# AltiumSTM32_Barunastra.net
KiCad netlist of a schematic drawn in Altium Designer
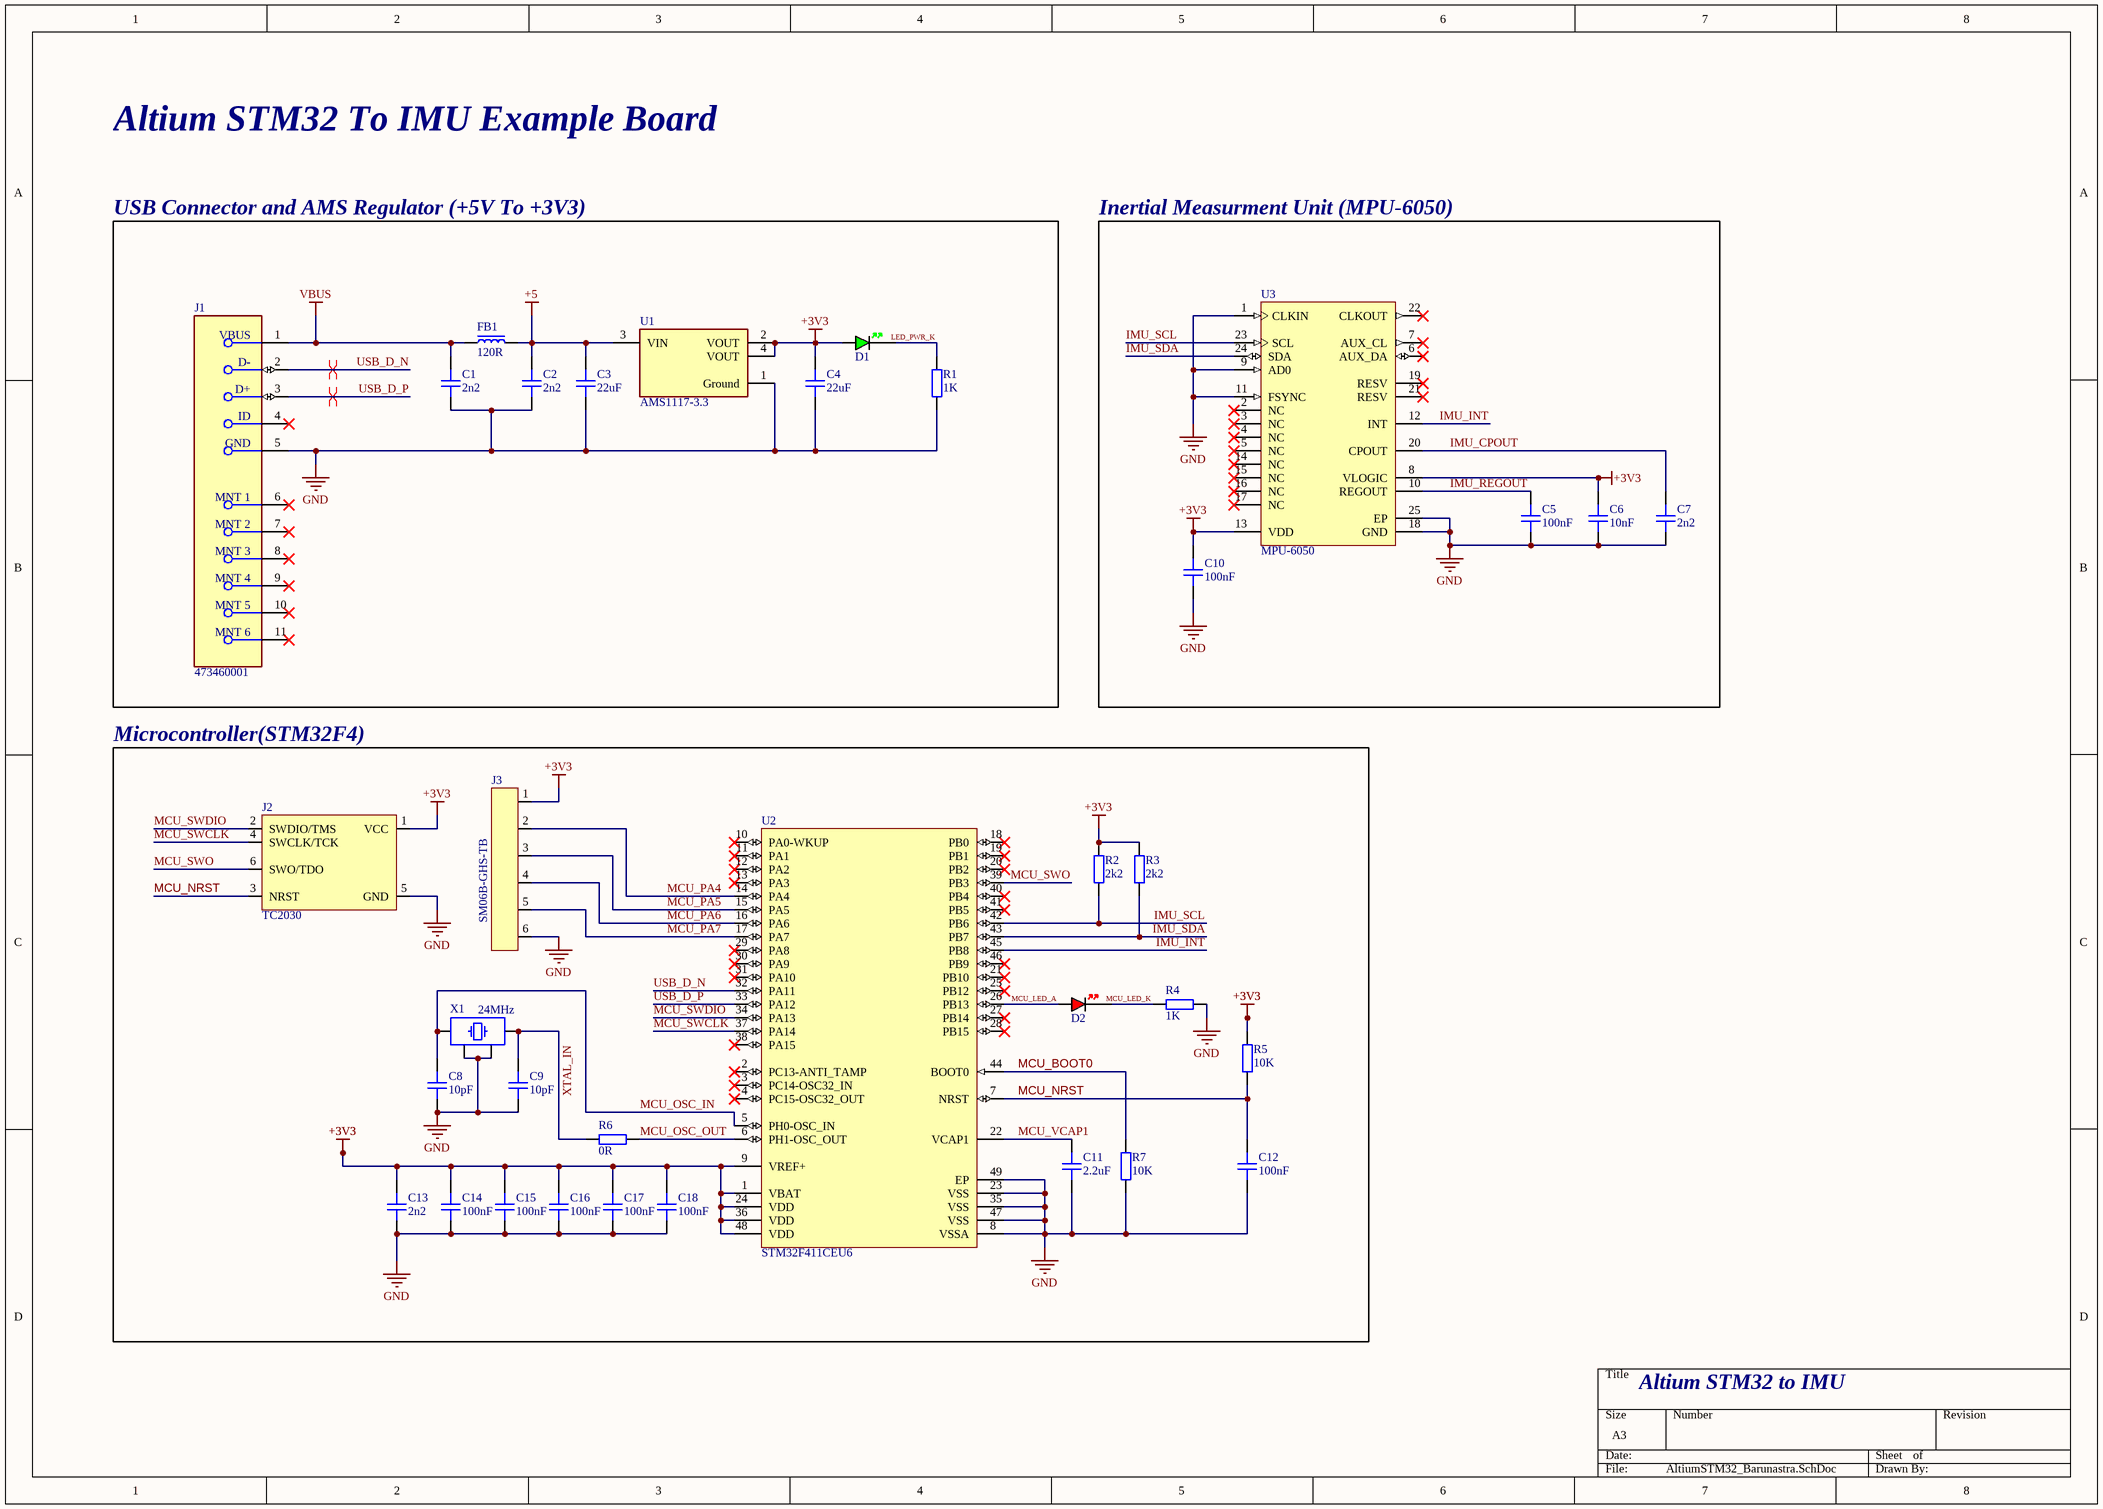
[diagram p0: AltiumSTM32_Barunastra.SchDoc]

(export (version "E")
  (design (tool "Eeschema 10.0.6"))
  (components
    (comp (ref "C1")
      (value "2n2")
      (footprint "CAP_0603")
      (description "Capacitor SMD 0603")
      (libsource (lib "Schematic-Lib-PhilsLab") (part "CAP_0603"))
    )
    (comp (ref "C2")
      (value "2n2")
      (footprint "CAP_0603")
      (description "Capacitor SMD 0603")
      (libsource (lib "Schematic-Lib-PhilsLab") (part "CAP_0603"))
    )
    (comp (ref "C3")
      (value "22uF")
      (footprint "CAP_0805")
      (description "Capacitor SMD 0805")
      (libsource (lib "Schematic-Lib-PhilsLab") (part "CAP_0805"))
    )
    (comp (ref "C4")
      (value "22uF")
      (footprint "CAP_0805")
      (description "Capacitor SMD 0805")
      (libsource (lib "Schematic-Lib-PhilsLab") (part "CAP_0805"))
    )
    (comp (ref "C5")
      (value "100nF")
      (footprint "CAP_0402")
      (description "Capacitor SMD 0402")
      (libsource (lib "Schematic-Lib-PhilsLab") (part "CAP_0402"))
    )
    (comp (ref "C6")
      (value "10nF")
      (footprint "CAP_0402")
      (description "Capacitor SMD 0402")
      (libsource (lib "Schematic-Lib-PhilsLab") (part "CAP_0402"))
    )
    (comp (ref "C7")
      (value "2n2")
      (footprint "CAP_0402")
      (description "Capacitor SMD 0402")
      (libsource (lib "Schematic-Lib-PhilsLab") (part "CAP_0402"))
    )
    (comp (ref "C8")
      (value "10pF")
      (footprint "CAP_0402")
      (description "Capacitor SMD 0402")
      (libsource (lib "Schematic-Lib-PhilsLab") (part "CAP_0402"))
    )
    (comp (ref "C9")
      (value "10pF")
      (footprint "CAP_0402")
      (description "Capacitor SMD 0402")
      (libsource (lib "Schematic-Lib-PhilsLab") (part "CAP_0402"))
    )
    (comp (ref "C10")
      (value "100nF")
      (footprint "CAP_0402")
      (description "Capacitor SMD 0402")
      (libsource (lib "Schematic-Lib-PhilsLab") (part "CAP_0402"))
    )
    (comp (ref "C11")
      (value "2.2uF")
      (footprint "CAP_0603")
      (description "Capacitor SMD 0603")
      (libsource (lib "Schematic-Lib-PhilsLab") (part "CAP_0603"))
    )
    (comp (ref "C12")
      (value "100nF")
      (footprint "CAP_0402")
      (description "Capacitor SMD 0402")
      (libsource (lib "Schematic-Lib-PhilsLab") (part "CAP_0402"))
    )
    (comp (ref "C13")
      (value "2n2")
      (footprint "CAP_0603")
      (description "Capacitor SMD 0603")
      (libsource (lib "Schematic-Lib-PhilsLab") (part "CAP_0603"))
    )
    (comp (ref "C14")
      (value "100nF")
      (footprint "CAP_0402")
      (description "Capacitor SMD 0402")
      (libsource (lib "Schematic-Lib-PhilsLab") (part "CAP_0402"))
    )
    (comp (ref "C15")
      (value "100nF")
      (footprint "CAP_0402")
      (description "Capacitor SMD 0402")
      (libsource (lib "Schematic-Lib-PhilsLab") (part "CAP_0402"))
    )
    (comp (ref "C16")
      (value "100nF")
      (footprint "CAP_0402")
      (description "Capacitor SMD 0402")
      (libsource (lib "Schematic-Lib-PhilsLab") (part "CAP_0402"))
    )
    (comp (ref "C17")
      (value "100nF")
      (footprint "CAP_0402")
      (description "Capacitor SMD 0402")
      (libsource (lib "Schematic-Lib-PhilsLab") (part "CAP_0402"))
    )
    (comp (ref "C18")
      (value "100nF")
      (footprint "CAP_0402")
      (description "Capacitor SMD 0402")
      (libsource (lib "Schematic-Lib-PhilsLab") (part "CAP_0402"))
    )
    (comp (ref "D1")
      (value "GREEN")
      (footprint "LED_0402_GREEN")
      (description "LED 0402 GREEN SMD")
      (libsource (lib "Schematic-Lib-PhilsLab") (part "LED_0402_GREEN"))
    )
    (comp (ref "D2")
      (value "RED")
      (footprint "LED_0402_RED")
      (description "LED 0402 RED SMD")
      (libsource (lib "Schematic-Lib-PhilsLab") (part "LED_0402_RED"))
    )
    (comp (ref "FB1")
      (value "120R")
      (footprint "FB_0603")
      (description "Ferrite Bead SMD 0603")
      (libsource (lib "Schematic-Lib-PhilsLab") (part "FB_0603"))
    )
    (comp (ref "J1")
      (value "473460001")
      (footprint "FP-473460001-MFG")
      (description "CONN RCPT USB2.0 MICRO B SMD R/A")
      (fields
        (field (name "OCTOPART") "https://octopart.com/47346-0001-molex-7164928")
        (field (name "MANUFACTURER") "Molex")
      )
      (libsource (lib "Altium Content Vault") (part "53ae1f1d9b557310b43ca686e5bb76a"))
    )
    (comp (ref "J2")
      (value "TC2030")
      (footprint "TC2030-FP")
      (description "Tag-Connect No-Solder SWD Debug Connector DO NOT PLACE")
      (fields (field (name "MANUFACTURER") "Tag-Connect"))
      (libsource (lib "Schematic-Lib-PhilsLab") (part "TC2030"))
    )
    (comp (ref "J3")
      (value "SM06B-GHS-TB")
      (footprint "SM06B-GHS-TB")
      (description "Header Connector 6 Position 1.25MM Pitch SMD Horizontal JST GH")
      (fields (field (name "MANUFACTURER") "JST"))
      (libsource (lib "Schematic-Lib-PhilsLab") (part "SM06B-GHS-TB"))
    )
    (comp (ref "R1")
      (value "1K")
      (footprint "RES_0402")
      (description "Resistor SMD 0402")
      (libsource (lib "Schematic-Lib-PhilsLab") (part "RES_0402"))
    )
    (comp (ref "R2")
      (value "2k2")
      (footprint "RES_0402")
      (description "Resistor SMD 0402")
      (libsource (lib "Schematic-Lib-PhilsLab") (part "RES_0402"))
    )
    (comp (ref "R3")
      (value "2k2")
      (footprint "RES_0402")
      (description "Resistor SMD 0402")
      (libsource (lib "Schematic-Lib-PhilsLab") (part "RES_0402"))
    )
    (comp (ref "R4")
      (value "1K")
      (footprint "RES_0402")
      (description "Resistor SMD 0402")
      (libsource (lib "Schematic-Lib-PhilsLab") (part "RES_0402"))
    )
    (comp (ref "R5")
      (value "10K")
      (footprint "RES_0402")
      (description "Resistor SMD 0402")
      (libsource (lib "Schematic-Lib-PhilsLab") (part "RES_0402"))
    )
    (comp (ref "R6")
      (value "0R")
      (footprint "RES_0402")
      (description "Resistor SMD 0402")
      (libsource (lib "Schematic-Lib-PhilsLab") (part "RES_0402"))
    )
    (comp (ref "R7")
      (value "10K")
      (footprint "RES_0402")
      (description "Resistor SMD 0402")
      (libsource (lib "Schematic-Lib-PhilsLab") (part "RES_0402"))
    )
    (comp (ref "U1")
      (value "AMS1117-3.3")
      (footprint "FP-AMS1117-IPC_C")
      (description "LDO Voltage Regulators 1A, 3.3V")
      (fields
        (field (name "OCTOPART") "https://octopart.com/ams1117-3.3-advanced+monolithic+systems-25899300")
        (field (name "MANUFACTURER") "Advanced Monolithic Systems")
      )
      (libsource (lib "Altium Content Vault") (part "8bdbb5f8e77002000e30dd2845d0354"))
    )
    (comp (ref "U2")
      (value "STM32F411CEU6")
      (footprint "STM-UFQFPN48_L")
      (libsource (lib "Altium Content Vault") (part "MC-ARM-STM32F411-UFQFPN48"))
    )
    (comp (ref "U3")
      (value "MPU-6050")
      (footprint "IS-QFN-24_V")
      (fields (field (name "MANUFACTURER") "InvenSense"))
      (libsource (lib "Altium Content Vault") (part "IS-MPU-6050-QFN-24"))
    )
    (comp (ref "X1")
      (value "24MHz")
      (footprint "XTAL_3225")
      (description "Crystal SMD 24MHz 10PPM 7pF 3225")
      (fields
        (field (name "MANUFACTURER") "Epson")
        (field (name "MANUFACTURER PART NUMBER") "TSX-3225 24.0000MF15X-AC")
      )
      (libsource (lib "Schematic-Lib-PhilsLab") (part "TSX-3225_24.0000MF15X-AC"))
    )
  )
  (nets
    (net (code "1") (name "+3V3") (class "Default")
      (node (ref "C10") (pin "2") (pinfunction "2_2") (pintype "passive"))
      (node (ref "C13") (pin "2") (pinfunction "2_2") (pintype "passive"))
      (node (ref "C14") (pin "2") (pinfunction "2_2") (pintype "passive"))
      (node (ref "C15") (pin "2") (pinfunction "2_2") (pintype "passive"))
      (node (ref "C16") (pin "2") (pinfunction "2_2") (pintype "passive"))
      (node (ref "C17") (pin "2") (pinfunction "2_2") (pintype "passive"))
      (node (ref "C18") (pin "2") (pinfunction "2_2") (pintype "passive"))
      (node (ref "C4") (pin "2") (pinfunction "2_2") (pintype "passive"))
      (node (ref "C6") (pin "2") (pinfunction "2_2") (pintype "passive"))
      (node (ref "D1") (pin "A") (pinfunction "A_A") (pintype "passive"))
      (node (ref "J2") (pin "1") (pinfunction "VCC_1") (pintype "passive"))
      (node (ref "J3") (pin "1") (pinfunction "1_1") (pintype "passive"))
      (node (ref "R2") (pin "2") (pinfunction "2_2") (pintype "passive"))
      (node (ref "R3") (pin "2") (pinfunction "2_2") (pintype "passive"))
      (node (ref "R5") (pin "2") (pinfunction "2_2") (pintype "passive"))
      (node (ref "U1") (pin "2") (pinfunction "VOUT_2") (pintype "passive"))
      (node (ref "U1") (pin "4") (pinfunction "VOUT_4") (pintype "passive"))
      (node (ref "U2") (pin "1") (pinfunction "VBAT_1") (pintype "power_in"))
      (node (ref "U2") (pin "24") (pinfunction "VDD_24") (pintype "power_in"))
      (node (ref "U2") (pin "36") (pinfunction "VDD_36") (pintype "power_in"))
      (node (ref "U2") (pin "48") (pinfunction "VDD_48") (pintype "power_in"))
      (node (ref "U2") (pin "9") (pinfunction "VREF+_9") (pintype "power_in"))
      (node (ref "U3") (pin "13") (pinfunction "VDD_13") (pintype "power_in"))
      (node (ref "U3") (pin "8") (pinfunction "VLOGIC_8") (pintype "power_in"))
    )
    (net (code "2") (name "+5") (class "Default")
      (node (ref "C2") (pin "2") (pinfunction "2_2") (pintype "passive"))
      (node (ref "C3") (pin "2") (pinfunction "2_2") (pintype "passive"))
      (node (ref "FB1") (pin "2") (pinfunction "2_2") (pintype "passive"))
      (node (ref "U1") (pin "3") (pinfunction "VIN_3") (pintype "power_in"))
    )
    (net (code "3") (name "/IMU_CPOUT") (class "Default")
      (node (ref "C7") (pin "2") (pinfunction "2_2") (pintype "passive"))
      (node (ref "U3") (pin "20") (pinfunction "CPOUT_20") (pintype "passive"))
    )
    (net (code "4") (name "/IMU_INT") (class "Default")
      (node (ref "U2") (pin "45") (pinfunction "PB8_45") (pintype "bidirectional"))
      (node (ref "U3") (pin "12") (pinfunction "INT_12") (pintype "open_collector"))
    )
    (net (code "5") (name "/IMU_REGOUT") (class "Default")
      (node (ref "C5") (pin "2") (pinfunction "2_2") (pintype "passive"))
      (node (ref "U3") (pin "10") (pinfunction "REGOUT_10") (pintype "passive"))
    )
    (net (code "6") (name "/IMU_SCL") (class "Default")
      (node (ref "R2") (pin "1") (pinfunction "1_1") (pintype "passive"))
      (node (ref "U2") (pin "42") (pinfunction "PB6_42") (pintype "bidirectional"))
      (node (ref "U3") (pin "23") (pinfunction "SCL_23") (pintype "input"))
    )
    (net (code "7") (name "/IMU_SDA") (class "Default")
      (node (ref "R3") (pin "1") (pinfunction "1_1") (pintype "passive"))
      (node (ref "U2") (pin "43") (pinfunction "PB7_43") (pintype "bidirectional"))
      (node (ref "U3") (pin "24") (pinfunction "SDA_24") (pintype "bidirectional"))
    )
    (net (code "8") (name "/LED_PWR_K") (class "Default")
      (node (ref "D1") (pin "K") (pinfunction "K_K") (pintype "passive"))
      (node (ref "R1") (pin "2") (pinfunction "2_2") (pintype "passive"))
    )
    (net (code "9") (name "/MCU_BOOT0") (class "Default")
      (node (ref "R7") (pin "2") (pinfunction "2_2") (pintype "passive"))
      (node (ref "U2") (pin "44") (pinfunction "BOOT0_44") (pintype "input"))
    )
    (net (code "10") (name "/MCU_LED_A") (class "Default")
      (node (ref "D2") (pin "A") (pinfunction "A_A") (pintype "passive"))
      (node (ref "U2") (pin "26") (pinfunction "PB13_26") (pintype "bidirectional"))
    )
    (net (code "11") (name "/MCU_LED_K") (class "Default")
      (node (ref "D2") (pin "K") (pinfunction "K_K") (pintype "passive"))
      (node (ref "R4") (pin "2") (pinfunction "2_2") (pintype "passive"))
    )
    (net (code "12") (name "/MCU_NRST") (class "Default")
      (node (ref "C12") (pin "2") (pinfunction "2_2") (pintype "passive"))
      (node (ref "J2") (pin "3") (pinfunction "NRST_3") (pintype "passive"))
      (node (ref "R5") (pin "1") (pinfunction "1_1") (pintype "passive"))
      (node (ref "U2") (pin "7") (pinfunction "NRST_7") (pintype "bidirectional"))
    )
    (net (code "13") (name "/MCU_OSC_IN") (class "Default")
      (node (ref "C8") (pin "2") (pinfunction "2_2") (pintype "passive"))
      (node (ref "U2") (pin "5") (pinfunction "PH0-OSC_IN_5") (pintype "bidirectional"))
      (node (ref "X1") (pin "1") (pinfunction "1_1") (pintype "passive"))
    )
    (net (code "14") (name "/MCU_OSC_OUT") (class "Default")
      (node (ref "R6") (pin "2") (pinfunction "2_2") (pintype "passive"))
      (node (ref "U2") (pin "6") (pinfunction "PH1-OSC_OUT_6") (pintype "bidirectional"))
    )
    (net (code "15") (name "/MCU_PA4") (class "Default")
      (node (ref "J3") (pin "2") (pinfunction "2_2") (pintype "passive"))
      (node (ref "U2") (pin "14") (pinfunction "PA4_14") (pintype "bidirectional"))
    )
    (net (code "16") (name "/MCU_PA5") (class "Default")
      (node (ref "J3") (pin "3") (pinfunction "3_3") (pintype "passive"))
      (node (ref "U2") (pin "15") (pinfunction "PA5_15") (pintype "bidirectional"))
    )
    (net (code "17") (name "/MCU_PA6") (class "Default")
      (node (ref "J3") (pin "4") (pinfunction "4_4") (pintype "passive"))
      (node (ref "U2") (pin "16") (pinfunction "PA6_16") (pintype "bidirectional"))
    )
    (net (code "18") (name "/MCU_PA7") (class "Default")
      (node (ref "J3") (pin "5") (pinfunction "5_5") (pintype "passive"))
      (node (ref "U2") (pin "17") (pinfunction "PA7_17") (pintype "bidirectional"))
    )
    (net (code "19") (name "/MCU_SWCLK") (class "Default")
      (node (ref "J2") (pin "4") (pinfunction "SWCLK/TCK_4") (pintype "passive"))
      (node (ref "U2") (pin "37") (pinfunction "PA14_37") (pintype "bidirectional"))
    )
    (net (code "20") (name "/MCU_SWDIO") (class "Default")
      (node (ref "J2") (pin "2") (pinfunction "SWDIO/TMS_2") (pintype "passive"))
      (node (ref "U2") (pin "34") (pinfunction "PA13_34") (pintype "bidirectional"))
    )
    (net (code "21") (name "/MCU_SWO") (class "Default")
      (node (ref "J2") (pin "6") (pinfunction "SWO/TDO_6") (pintype "passive"))
      (node (ref "U2") (pin "39") (pinfunction "PB3_39") (pintype "bidirectional"))
    )
    (net (code "22") (name "/MCU_VCAP1") (class "Default")
      (node (ref "C11") (pin "2") (pinfunction "2_2") (pintype "passive"))
      (node (ref "U2") (pin "22") (pinfunction "VCAP1_22") (pintype "passive"))
    )
    (net (code "23") (name "/USB_D_N") (class "Default")
      (node (ref "J1") (pin "2") (pinfunction "D-_2") (pintype "bidirectional"))
      (node (ref "U2") (pin "32") (pinfunction "PA11_32") (pintype "bidirectional"))
    )
    (net (code "24") (name "/USB_D_P") (class "Default")
      (node (ref "J1") (pin "3") (pinfunction "D+_3") (pintype "bidirectional"))
      (node (ref "U2") (pin "33") (pinfunction "PA12_33") (pintype "bidirectional"))
    )
    (net (code "25") (name "/XTAL_IN") (class "Default")
      (node (ref "C9") (pin "2") (pinfunction "2_2") (pintype "passive"))
      (node (ref "R6") (pin "1") (pinfunction "1_1") (pintype "passive"))
      (node (ref "X1") (pin "3") (pinfunction "3_3") (pintype "passive"))
    )
    (net (code "26") (name "GND") (class "Default")
      (node (ref "C1") (pin "1") (pinfunction "1_1") (pintype "passive"))
      (node (ref "C10") (pin "1") (pinfunction "1_1") (pintype "passive"))
      (node (ref "C11") (pin "1") (pinfunction "1_1") (pintype "passive"))
      (node (ref "C12") (pin "1") (pinfunction "1_1") (pintype "passive"))
      (node (ref "C13") (pin "1") (pinfunction "1_1") (pintype "passive"))
      (node (ref "C14") (pin "1") (pinfunction "1_1") (pintype "passive"))
      (node (ref "C15") (pin "1") (pinfunction "1_1") (pintype "passive"))
      (node (ref "C16") (pin "1") (pinfunction "1_1") (pintype "passive"))
      (node (ref "C17") (pin "1") (pinfunction "1_1") (pintype "passive"))
      (node (ref "C18") (pin "1") (pinfunction "1_1") (pintype "passive"))
      (node (ref "C2") (pin "1") (pinfunction "1_1") (pintype "passive"))
      (node (ref "C3") (pin "1") (pinfunction "1_1") (pintype "passive"))
      (node (ref "C4") (pin "1") (pinfunction "1_1") (pintype "passive"))
      (node (ref "C5") (pin "1") (pinfunction "1_1") (pintype "passive"))
      (node (ref "C6") (pin "1") (pinfunction "1_1") (pintype "passive"))
      (node (ref "C7") (pin "1") (pinfunction "1_1") (pintype "passive"))
      (node (ref "C8") (pin "1") (pinfunction "1_1") (pintype "passive"))
      (node (ref "C9") (pin "1") (pinfunction "1_1") (pintype "passive"))
      (node (ref "J1") (pin "5") (pinfunction "GND_5") (pintype "power_in"))
      (node (ref "J2") (pin "5") (pinfunction "GND_5") (pintype "passive"))
      (node (ref "J3") (pin "6") (pinfunction "6_6") (pintype "passive"))
      (node (ref "R1") (pin "1") (pinfunction "1_1") (pintype "passive"))
      (node (ref "R4") (pin "1") (pinfunction "1_1") (pintype "passive"))
      (node (ref "R7") (pin "1") (pinfunction "1_1") (pintype "passive"))
      (node (ref "U1") (pin "1") (pinfunction "Ground_1") (pintype "power_in"))
      (node (ref "U2") (pin "23") (pinfunction "VSS_23") (pintype "power_in"))
      (node (ref "U2") (pin "35") (pinfunction "VSS_35") (pintype "power_in"))
      (node (ref "U2") (pin "47") (pinfunction "VSS_47") (pintype "power_in"))
      (node (ref "U2") (pin "49") (pinfunction "EP_49") (pintype "power_in"))
      (node (ref "U2") (pin "8") (pinfunction "VSSA_8") (pintype "power_in"))
      (node (ref "U3") (pin "1") (pinfunction "CLKIN_1") (pintype "input"))
      (node (ref "U3") (pin "11") (pinfunction "FSYNC_11") (pintype "input"))
      (node (ref "U3") (pin "18") (pinfunction "GND_18") (pintype "power_in"))
      (node (ref "U3") (pin "25") (pinfunction "EP_25") (pintype "power_in"))
      (node (ref "U3") (pin "9") (pinfunction "AD0_9") (pintype "input"))
      (node (ref "X1") (pin "2") (pinfunction "2_2") (pintype "passive"))
      (node (ref "X1") (pin "4") (pinfunction "4_4") (pintype "passive"))
    )
    (net (code "27") (name "VBUS") (class "Default")
      (node (ref "C1") (pin "2") (pinfunction "2_2") (pintype "passive"))
      (node (ref "FB1") (pin "1") (pinfunction "1_1") (pintype "passive"))
      (node (ref "J1") (pin "1") (pinfunction "VBUS_1") (pintype "power_in"))
    )
    (net (code "28") (name "unconnected-(J1-ID-Pad4)") (class "Default")
      (node (ref "J1") (pin "4") (pinfunction "ID_4") (pintype "passive+no_connect"))
    )
    (net (code "29") (name "unconnected-(J1-MNT_1-Pad6)") (class "Default")
      (node (ref "J1") (pin "6") (pinfunction "MNT_1_6") (pintype "passive+no_connect"))
    )
    (net (code "30") (name "unconnected-(J1-MNT_2-Pad7)") (class "Default")
      (node (ref "J1") (pin "7") (pinfunction "MNT_2_7") (pintype "passive+no_connect"))
    )
    (net (code "31") (name "unconnected-(J1-MNT_3-Pad8)") (class "Default")
      (node (ref "J1") (pin "8") (pinfunction "MNT_3_8") (pintype "passive+no_connect"))
    )
    (net (code "32") (name "unconnected-(J1-MNT_4-Pad9)") (class "Default")
      (node (ref "J1") (pin "9") (pinfunction "MNT_4_9") (pintype "passive+no_connect"))
    )
    (net (code "33") (name "unconnected-(J1-MNT_5-Pad10)") (class "Default")
      (node (ref "J1") (pin "10") (pinfunction "MNT_5_10") (pintype "passive+no_connect"))
    )
    (net (code "34") (name "unconnected-(J1-MNT_6-Pad11)") (class "Default")
      (node (ref "J1") (pin "11") (pinfunction "MNT_6_11") (pintype "passive+no_connect"))
    )
    (net (code "35") (name "unconnected-(U2-PA0-WKUP-Pad10)") (class "Default")
      (node (ref "U2") (pin "10") (pinfunction "PA0-WKUP_10") (pintype "bidirectional+no_connect"))
    )
    (net (code "36") (name "unconnected-(U2-PA1-Pad11)") (class "Default")
      (node (ref "U2") (pin "11") (pinfunction "PA1_11") (pintype "bidirectional+no_connect"))
    )
    (net (code "37") (name "unconnected-(U2-PA2-Pad12)") (class "Default")
      (node (ref "U2") (pin "12") (pinfunction "PA2_12") (pintype "bidirectional+no_connect"))
    )
    (net (code "38") (name "unconnected-(U2-PA3-Pad13)") (class "Default")
      (node (ref "U2") (pin "13") (pinfunction "PA3_13") (pintype "bidirectional+no_connect"))
    )
    (net (code "39") (name "unconnected-(U2-PA8-Pad29)") (class "Default")
      (node (ref "U2") (pin "29") (pinfunction "PA8_29") (pintype "bidirectional+no_connect"))
    )
    (net (code "40") (name "unconnected-(U2-PA9-Pad30)") (class "Default")
      (node (ref "U2") (pin "30") (pinfunction "PA9_30") (pintype "bidirectional+no_connect"))
    )
    (net (code "41") (name "unconnected-(U2-PA10-Pad31)") (class "Default")
      (node (ref "U2") (pin "31") (pinfunction "PA10_31") (pintype "bidirectional+no_connect"))
    )
    (net (code "42") (name "unconnected-(U2-PA15-Pad38)") (class "Default")
      (node (ref "U2") (pin "38") (pinfunction "PA15_38") (pintype "bidirectional+no_connect"))
    )
    (net (code "43") (name "unconnected-(U2-PB0-Pad18)") (class "Default")
      (node (ref "U2") (pin "18") (pinfunction "PB0_18") (pintype "bidirectional+no_connect"))
    )
    (net (code "44") (name "unconnected-(U2-PB1-Pad19)") (class "Default")
      (node (ref "U2") (pin "19") (pinfunction "PB1_19") (pintype "bidirectional+no_connect"))
    )
    (net (code "45") (name "unconnected-(U2-PB2-Pad20)") (class "Default")
      (node (ref "U2") (pin "20") (pinfunction "PB2_20") (pintype "bidirectional+no_connect"))
    )
    (net (code "46") (name "unconnected-(U2-PB4-Pad40)") (class "Default")
      (node (ref "U2") (pin "40") (pinfunction "PB4_40") (pintype "bidirectional+no_connect"))
    )
    (net (code "47") (name "unconnected-(U2-PB5-Pad41)") (class "Default")
      (node (ref "U2") (pin "41") (pinfunction "PB5_41") (pintype "bidirectional+no_connect"))
    )
    (net (code "48") (name "unconnected-(U2-PB9-Pad46)") (class "Default")
      (node (ref "U2") (pin "46") (pinfunction "PB9_46") (pintype "bidirectional+no_connect"))
    )
    (net (code "49") (name "unconnected-(U2-PB10-Pad21)") (class "Default")
      (node (ref "U2") (pin "21") (pinfunction "PB10_21") (pintype "bidirectional+no_connect"))
    )
    (net (code "50") (name "unconnected-(U2-PB12-Pad25)") (class "Default")
      (node (ref "U2") (pin "25") (pinfunction "PB12_25") (pintype "bidirectional+no_connect"))
    )
    (net (code "51") (name "unconnected-(U2-PB14-Pad27)") (class "Default")
      (node (ref "U2") (pin "27") (pinfunction "PB14_27") (pintype "bidirectional+no_connect"))
    )
    (net (code "52") (name "unconnected-(U2-PB15-Pad28)") (class "Default")
      (node (ref "U2") (pin "28") (pinfunction "PB15_28") (pintype "bidirectional+no_connect"))
    )
    (net (code "53") (name "unconnected-(U2-PC13-ANTI_TAMP-Pad2)") (class "Default")
      (node (ref "U2") (pin "2") (pinfunction "PC13-ANTI_TAMP_2") (pintype "bidirectional+no_connect"))
    )
    (net (code "54") (name "unconnected-(U2-PC14-OSC32_IN-Pad3)") (class "Default")
      (node (ref "U2") (pin "3") (pinfunction "PC14-OSC32_IN_3") (pintype "bidirectional+no_connect"))
    )
    (net (code "55") (name "unconnected-(U2-PC15-OSC32_OUT-Pad4)") (class "Default")
      (node (ref "U2") (pin "4") (pinfunction "PC15-OSC32_OUT_4") (pintype "bidirectional+no_connect"))
    )
    (net (code "56") (name "unconnected-(U3-AUX_CL-Pad7)") (class "Default")
      (node (ref "U3") (pin "7") (pinfunction "AUX_CL_7") (pintype "output+no_connect"))
    )
    (net (code "57") (name "unconnected-(U3-AUX_DA-Pad6)") (class "Default")
      (node (ref "U3") (pin "6") (pinfunction "AUX_DA_6") (pintype "bidirectional+no_connect"))
    )
    (net (code "58") (name "unconnected-(U3-CLKOUT-Pad22)") (class "Default")
      (node (ref "U3") (pin "22") (pinfunction "CLKOUT_22") (pintype "output+no_connect"))
    )
    (net (code "59") (name "unconnected-(U3-NC-Pad2)") (class "Default")
      (node (ref "U3") (pin "2") (pinfunction "NC_2") (pintype "passive+no_connect"))
    )
    (net (code "60") (name "unconnected-(U3-NC-Pad3)") (class "Default")
      (node (ref "U3") (pin "3") (pinfunction "NC_3") (pintype "passive+no_connect"))
    )
    (net (code "61") (name "unconnected-(U3-NC-Pad4)") (class "Default")
      (node (ref "U3") (pin "4") (pinfunction "NC_4") (pintype "passive+no_connect"))
    )
    (net (code "62") (name "unconnected-(U3-NC-Pad5)") (class "Default")
      (node (ref "U3") (pin "5") (pinfunction "NC_5") (pintype "passive+no_connect"))
    )
    (net (code "63") (name "unconnected-(U3-NC-Pad14)") (class "Default")
      (node (ref "U3") (pin "14") (pinfunction "NC_14") (pintype "passive+no_connect"))
    )
    (net (code "64") (name "unconnected-(U3-NC-Pad15)") (class "Default")
      (node (ref "U3") (pin "15") (pinfunction "NC_15") (pintype "passive+no_connect"))
    )
    (net (code "65") (name "unconnected-(U3-NC-Pad16)") (class "Default")
      (node (ref "U3") (pin "16") (pinfunction "NC_16") (pintype "passive+no_connect"))
    )
    (net (code "66") (name "unconnected-(U3-NC-Pad17)") (class "Default")
      (node (ref "U3") (pin "17") (pinfunction "NC_17") (pintype "passive+no_connect"))
    )
    (net (code "67") (name "unconnected-(U3-RESV-Pad19)") (class "Default")
      (node (ref "U3") (pin "19") (pinfunction "RESV_19") (pintype "passive+no_connect"))
    )
    (net (code "68") (name "unconnected-(U3-RESV-Pad21)") (class "Default")
      (node (ref "U3") (pin "21") (pinfunction "RESV_21") (pintype "passive+no_connect"))
    )
  )
)
